# OSSI-1_Interface_Board_0.net
KiCad netlist of a schematic drawn in Altium Designer
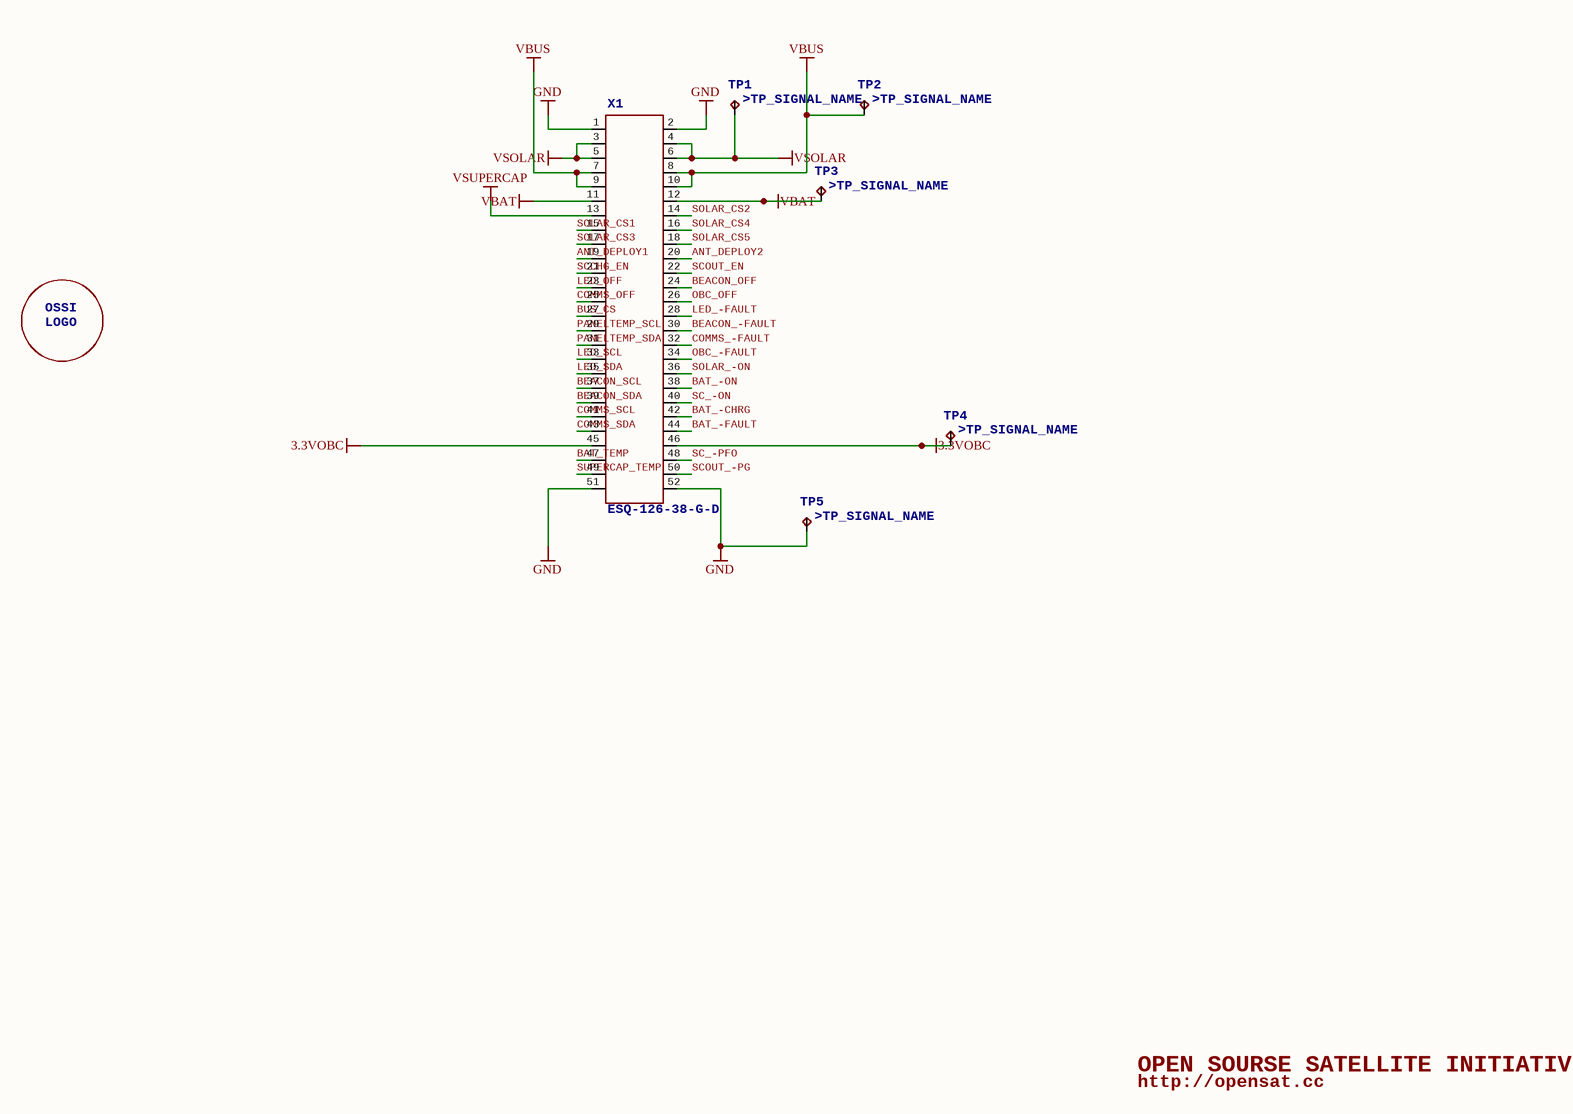
[diagram p0: OSSI-1 Interface Board_0.SchDoc]

(export (version "E")
  (design (tool "Eeschema 10.0.6"))
  (components
    (comp (ref "TP1")
      (value "TP")
      (footprint "TP-13")
      (fields (field (name ">NAME") "TP1") (field (name ">TP_SIGNAL_NAME") ">TP_SIGNAL_NAME"))
      (libsource (lib "OSSI") (part "TP"))
    )
    (comp (ref "TP2")
      (value "TP")
      (footprint "TP-13")
      (fields (field (name ">NAME") "TP2") (field (name ">TP_SIGNAL_NAME") ">TP_SIGNAL_NAME"))
      (libsource (lib "OSSI") (part "TP"))
    )
    (comp (ref "TP3")
      (value "TP")
      (footprint "TP-13")
      (fields (field (name ">NAME") "TP3") (field (name ">TP_SIGNAL_NAME") ">TP_SIGNAL_NAME"))
      (libsource (lib "OSSI") (part "TP"))
    )
    (comp (ref "TP4")
      (value "TP")
      (footprint "TP-13")
      (fields (field (name ">NAME") "TP4") (field (name ">TP_SIGNAL_NAME") ">TP_SIGNAL_NAME"))
      (libsource (lib "OSSI") (part "TP"))
    )
    (comp (ref "TP5")
      (value "TP")
      (footprint "TP-13")
      (fields (field (name ">NAME") "TP5") (field (name ">TP_SIGNAL_NAME") ">TP_SIGNAL_NAME"))
      (libsource (lib "OSSI") (part "TP"))
    )
    (comp (ref "U$1")
      (value "OSSILOGO-10")
      (footprint "OSSILOGO1010")
      (fields (field (name "OSSI") "OSSI") (field (name "LOGO") "LOGO"))
      (libsource (lib "OSSI") (part "OSSILOGO-10"))
    )
    (comp (ref "X1")
      (value "ESQ-126-38-G-D")
      (footprint "ESQ-126-XX-X-D")
      (fields (field (name ">NAME") "X1") (field (name ">VALUE") "ESQ-126-38-G-D"))
      (libsource (lib "OSSI") (part "ESQ-126-38-G-D"))
    )
  )
  (nets
    (net (code "1") (name "/ANT_DEPLOY1") (class "Default")
      (node (ref "X1") (pin "19") (pinfunction "19_19") (pintype "passive"))
    )
    (net (code "2") (name "/ANT_DEPLOY2") (class "Default")
      (node (ref "X1") (pin "20") (pinfunction "20_20") (pintype "passive"))
    )
    (net (code "3") (name "/BAT_-CHRG") (class "Default")
      (node (ref "X1") (pin "42") (pinfunction "42_42") (pintype "passive"))
    )
    (net (code "4") (name "/BAT_-FAULT") (class "Default")
      (node (ref "X1") (pin "44") (pinfunction "44_44") (pintype "passive"))
    )
    (net (code "5") (name "/BAT_-ON") (class "Default")
      (node (ref "X1") (pin "38") (pinfunction "38_38") (pintype "passive"))
    )
    (net (code "6") (name "/BAT_TEMP") (class "Default")
      (node (ref "X1") (pin "47") (pinfunction "47_47") (pintype "passive"))
    )
    (net (code "7") (name "/BEACON_-FAULT") (class "Default")
      (node (ref "X1") (pin "30") (pinfunction "30_30") (pintype "passive"))
    )
    (net (code "8") (name "/BEACON_OFF") (class "Default")
      (node (ref "X1") (pin "24") (pinfunction "24_24") (pintype "passive"))
    )
    (net (code "9") (name "/BEACON_SCL") (class "Default")
      (node (ref "X1") (pin "37") (pinfunction "37_37") (pintype "passive"))
    )
    (net (code "10") (name "/BEACON_SDA") (class "Default")
      (node (ref "X1") (pin "39") (pinfunction "39_39") (pintype "passive"))
    )
    (net (code "11") (name "/BUS_CS") (class "Default")
      (node (ref "X1") (pin "27") (pinfunction "27_27") (pintype "passive"))
    )
    (net (code "12") (name "/COMMS_-FAULT") (class "Default")
      (node (ref "X1") (pin "32") (pinfunction "32_32") (pintype "passive"))
    )
    (net (code "13") (name "/COMMS_OFF") (class "Default")
      (node (ref "X1") (pin "25") (pinfunction "25_25") (pintype "passive"))
    )
    (net (code "14") (name "/COMMS_SCL") (class "Default")
      (node (ref "X1") (pin "41") (pinfunction "41_41") (pintype "passive"))
    )
    (net (code "15") (name "/COMMS_SDA") (class "Default")
      (node (ref "X1") (pin "43") (pinfunction "43_43") (pintype "passive"))
    )
    (net (code "16") (name "/LED_-FAULT") (class "Default")
      (node (ref "X1") (pin "28") (pinfunction "28_28") (pintype "passive"))
    )
    (net (code "17") (name "/LED_OFF") (class "Default")
      (node (ref "X1") (pin "23") (pinfunction "23_23") (pintype "passive"))
    )
    (net (code "18") (name "/LED_SCL") (class "Default")
      (node (ref "X1") (pin "33") (pinfunction "33_33") (pintype "passive"))
    )
    (net (code "19") (name "/LED_SDA") (class "Default")
      (node (ref "X1") (pin "35") (pinfunction "35_35") (pintype "passive"))
    )
    (net (code "20") (name "/OBC_-FAULT") (class "Default")
      (node (ref "X1") (pin "34") (pinfunction "34_34") (pintype "passive"))
    )
    (net (code "21") (name "/OBC_OFF") (class "Default")
      (node (ref "X1") (pin "26") (pinfunction "26_26") (pintype "passive"))
    )
    (net (code "22") (name "/PANELTEMP_SCL") (class "Default")
      (node (ref "X1") (pin "29") (pinfunction "29_29") (pintype "passive"))
    )
    (net (code "23") (name "/PANELTEMP_SDA") (class "Default")
      (node (ref "X1") (pin "31") (pinfunction "31_31") (pintype "passive"))
    )
    (net (code "24") (name "/SCCHG_EN") (class "Default")
      (node (ref "X1") (pin "21") (pinfunction "21_21") (pintype "passive"))
    )
    (net (code "25") (name "/SCOUT_-PG") (class "Default")
      (node (ref "X1") (pin "50") (pinfunction "50_50") (pintype "passive"))
    )
    (net (code "26") (name "/SCOUT_EN") (class "Default")
      (node (ref "X1") (pin "22") (pinfunction "22_22") (pintype "passive"))
    )
    (net (code "27") (name "/SC_-ON") (class "Default")
      (node (ref "X1") (pin "40") (pinfunction "40_40") (pintype "passive"))
    )
    (net (code "28") (name "/SC_-PFO") (class "Default")
      (node (ref "X1") (pin "48") (pinfunction "48_48") (pintype "passive"))
    )
    (net (code "29") (name "/SOLAR_-ON") (class "Default")
      (node (ref "X1") (pin "36") (pinfunction "36_36") (pintype "passive"))
    )
    (net (code "30") (name "/SOLAR_CS1") (class "Default")
      (node (ref "X1") (pin "15") (pinfunction "15_15") (pintype "passive"))
    )
    (net (code "31") (name "/SOLAR_CS2") (class "Default")
      (node (ref "X1") (pin "14") (pinfunction "14_14") (pintype "passive"))
    )
    (net (code "32") (name "/SOLAR_CS3") (class "Default")
      (node (ref "X1") (pin "17") (pinfunction "17_17") (pintype "passive"))
    )
    (net (code "33") (name "/SOLAR_CS4") (class "Default")
      (node (ref "X1") (pin "16") (pinfunction "16_16") (pintype "passive"))
    )
    (net (code "34") (name "/SOLAR_CS5") (class "Default")
      (node (ref "X1") (pin "18") (pinfunction "18_18") (pintype "passive"))
    )
    (net (code "35") (name "/SUPERCAP_TEMP") (class "Default")
      (node (ref "X1") (pin "49") (pinfunction "49_49") (pintype "passive"))
    )
    (net (code "36") (name "3.3VOBC") (class "Default")
      (node (ref "TP4") (pin "TP") (pinfunction "TP_TP") (pintype "passive"))
      (node (ref "X1") (pin "45") (pinfunction "45_45") (pintype "passive"))
      (node (ref "X1") (pin "46") (pinfunction "46_46") (pintype "passive"))
    )
    (net (code "37") (name "GND") (class "Default")
      (node (ref "TP5") (pin "TP") (pinfunction "TP_TP") (pintype "passive"))
      (node (ref "X1") (pin "1") (pinfunction "1_1") (pintype "passive"))
      (node (ref "X1") (pin "2") (pinfunction "2_2") (pintype "passive"))
      (node (ref "X1") (pin "51") (pinfunction "51_51") (pintype "passive"))
      (node (ref "X1") (pin "52") (pinfunction "52_52") (pintype "passive"))
    )
    (net (code "38") (name "VBAT") (class "Default")
      (node (ref "TP3") (pin "TP") (pinfunction "TP_TP") (pintype "passive"))
      (node (ref "X1") (pin "11") (pinfunction "11_11") (pintype "passive"))
      (node (ref "X1") (pin "12") (pinfunction "12_12") (pintype "passive"))
    )
    (net (code "39") (name "VBUS") (class "Default")
      (node (ref "TP2") (pin "TP") (pinfunction "TP_TP") (pintype "passive"))
      (node (ref "X1") (pin "10") (pinfunction "10_10") (pintype "passive"))
      (node (ref "X1") (pin "7") (pinfunction "7_7") (pintype "passive"))
      (node (ref "X1") (pin "8") (pinfunction "8_8") (pintype "passive"))
      (node (ref "X1") (pin "9") (pinfunction "9_9") (pintype "passive"))
    )
    (net (code "40") (name "VSOLAR") (class "Default")
      (node (ref "TP1") (pin "TP") (pinfunction "TP_TP") (pintype "passive"))
      (node (ref "X1") (pin "3") (pinfunction "3_3") (pintype "passive"))
      (node (ref "X1") (pin "4") (pinfunction "4_4") (pintype "passive"))
      (node (ref "X1") (pin "5") (pinfunction "5_5") (pintype "passive"))
      (node (ref "X1") (pin "6") (pinfunction "6_6") (pintype "passive"))
    )
    (net (code "41") (name "VSUPERCAP") (class "Default")
      (node (ref "X1") (pin "13") (pinfunction "13_13") (pintype "passive"))
    )
  )
)
